# TASK1_1_SCHEM.net
KiCad netlist of a schematic drawn in Altium Designer
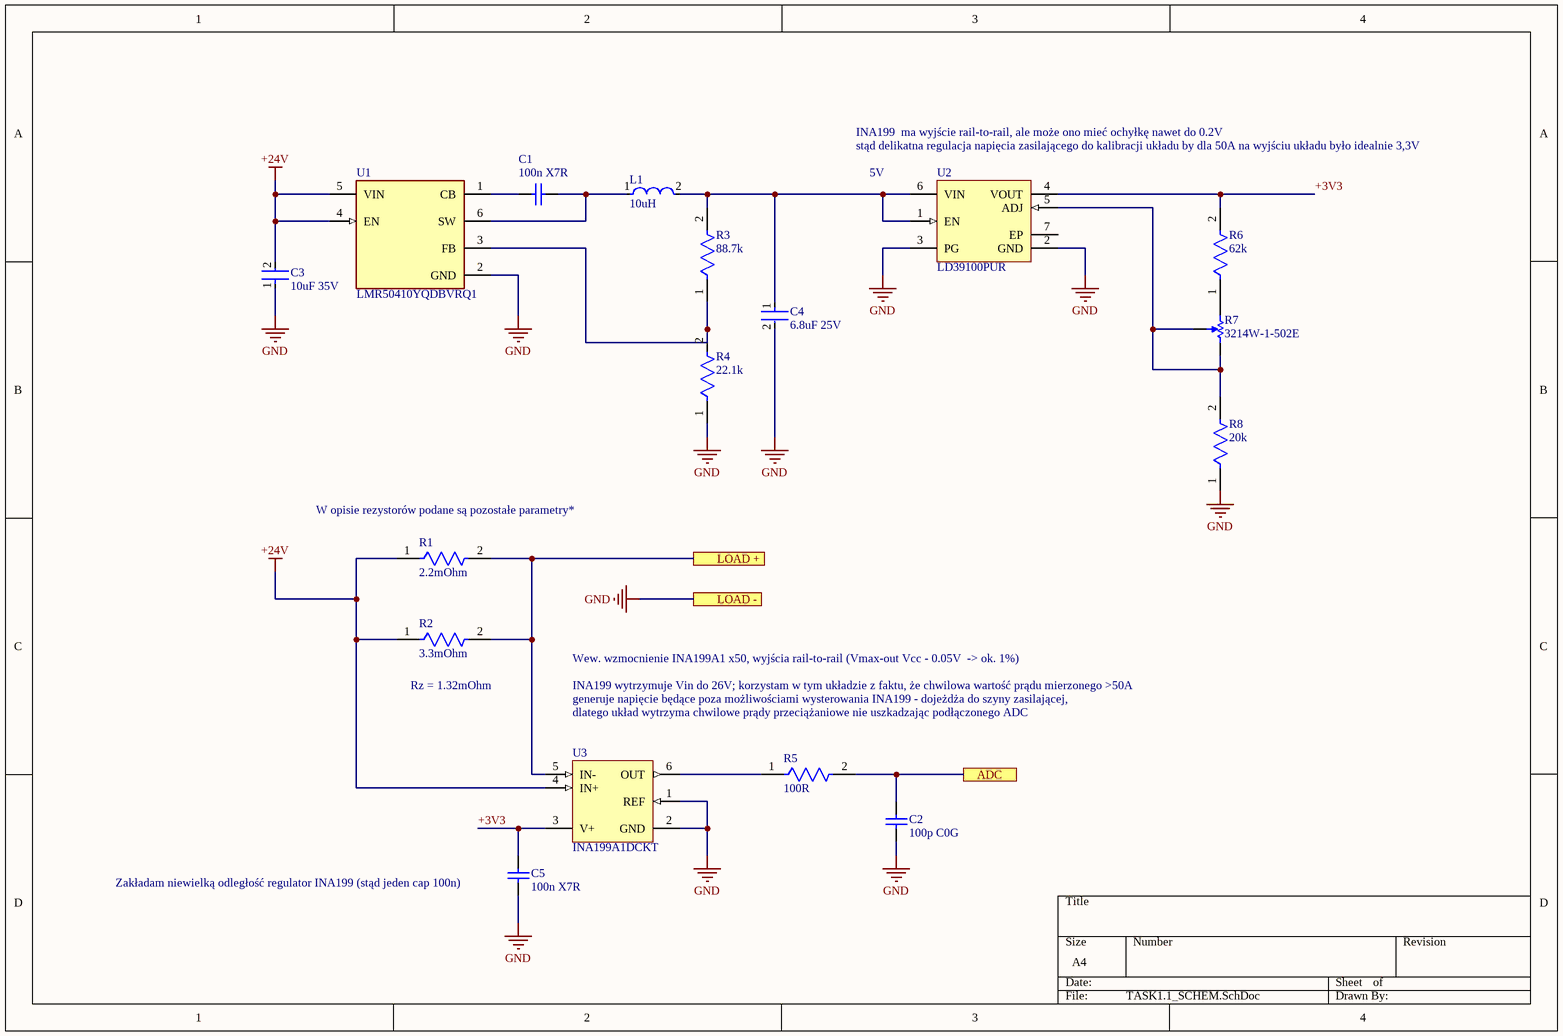
[diagram p0: TASK1.1_SCHEM.SchDoc]

(export (version "E")
  (design (tool "Eeschema 10.0.6"))
  (components
    (comp (ref "C1")
      (value "100n X7R")
      (footprint "CAPC1608X90X35LL15T15")
      (fields
        (field (name "MANUFACTURER") "AVX Interconnect / Elco")
        (field (name "PART NUMBER") "LD035C104KAB2A")
      )
      (libsource (lib "Altium Content Vault") (part "CAP"))
    )
    (comp (ref "C2")
      (value "100p C0G")
      (footprint "CAPC1608X95X40ML15T15")
      (fields (field (name "MANUFACTURER") "Vitramon") (field (name "PART NUMBER") "VJ0603A101JXACW1BC"))
      (libsource (lib "Altium Content Vault") (part "CAP"))
    )
    (comp (ref "C3")
      (value "10uF 35V")
      (footprint "FP-C3216-160-0_2-IPC_C")
      (description "Multilayer Ceramic Capacitors 10uF ±20% 35V X7R SMD 1206")
      (fields (field (name "TOLERANCE") "20%"))
      (libsource (lib "Altium Content Vault") (part "11868f565c42a9108669ba33697ecf6"))
    )
    (comp (ref "C4")
      (value "6.8uF 25V")
      (footprint "FP-C2012-125-0_2-IPC_A")
      (description "Multilayer Ceramic Capacitors 6.8μF ±20% 25V X5R SMD 0805")
      (fields (field (name "TOLERANCE") "20%"))
      (libsource (lib "Altium Content Vault") (part "b4654b650e69147ec39a6b967a45e02"))
    )
    (comp (ref "C5")
      (value "100n X7R")
      (footprint "CAPC1608X90X35LL15T15")
      (fields
        (field (name "MANUFACTURER") "AVX Interconnect / Elco")
        (field (name "PART NUMBER") "LD035C104KAB2A")
      )
      (libsource (lib "Altium Content Vault") (part "CAP"))
    )
    (comp (ref "L1")
      (value "10uH")
      (footprint "FP-NR6045-MFG")
      (description "Shielded Wirewound Inductor 10uH 20% 2.8A 59.8mΩ SMD")
      (fields (field (name "TOLERANCE") "20%"))
      (libsource (lib "Altium Content Vault") (part "725321dda6339637d4d059423bc1c3c"))
    )
    (comp (ref "R1")
      (value "2.2mOhm")
      (footprint "FP-CRCW2512-e3-IPC_C")
      (description "WSL25122L200FEA18\r\nRES 0.0022 OHM 1% 2W 2512")
      (fields (field (name "TOLERANCE") "1%"))
      (libsource (lib "Altium Content Vault") (part "1029c3af85768c4190bb7ad29bc67b5"))
    )
    (comp (ref "R2")
      (value "3.3mOhm")
      (footprint "FP-CRCW2512-e3-IPC_C")
      (description "WSL28163L300FEH\r\nRES 0.0033 OHM 1% 2W 2816")
      (fields (field (name "TOLERANCE") "1%"))
      (libsource (lib "Altium Content Vault") (part "1029c3af85768c4190bb7ad29bc67b5"))
    )
    (comp (ref "R3")
      (value "88.7k")
      (footprint "FP-CRCW0603-e3-MFG")
      (description "RES Thick Film, 88.7kΩ, 1%, 0.1W, 100ppm/°C, 0603")
      (fields (field (name "TOLERANCE") "1%"))
      (libsource (lib "Altium Content Vault") (part "1029c3af85768c4190bb7ad29bc67b5"))
    )
    (comp (ref "R4")
      (value "22.1k")
      (footprint "FP-RP73P-1J-MFG")
      (description "RES SMD 22.1K OHM 0.1% 1/6W 0603")
      (fields (field (name "TOLERANCE") "0.001") (field (name "MANUFACTURER") "TE Connectivity"))
      (libsource (lib "Altium Content Vault") (part "1029c3af85768c4190bb7ad29bc67b5"))
    )
    (comp (ref "R5")
      (value "100R")
      (footprint "FP-ERA3A-IPC_B")
      (description "RES SMD 100 OHM 0.1% 1/10W 0603")
      (fields (field (name "TOLERANCE") "0.1%"))
      (libsource (lib "Altium Content Vault") (part "1029c3af85768c4190bb7ad29bc67b5"))
    )
    (comp (ref "R6")
      (value "62k")
      (footprint "FP-ERJ2RK-MFG")
      (fields (field (name "TOLERANCE") "1%"))
      (libsource (lib "Altium Content Vault") (part "1029c3af85768c4190bb7ad29bc67b5"))
    )
    (comp (ref "R7")
      (value "3214W-1-502E")
      (footprint "BOUR-3214W_V")
      (fields (field (name "MANUFACTURER") "Bourns"))
      (libsource (lib "Altium Content Vault") (part "RES-ADJ-3_A"))
    )
    (comp (ref "R8")
      (value "20k")
      (footprint "FP-RC0402-0_4-MFG")
      (fields (field (name "TOLERANCE") "1%"))
      (libsource (lib "Altium Content Vault") (part "1029c3af85768c4190bb7ad29bc67b5"))
    )
    (comp (ref "U1")
      (value "LMR50410YQDBVRQ1")
      (footprint "FP-DBV0006A-MFG")
      (description "NIXON PLUS-LMR50410YQDBVRQ1")
      (libsource (lib "Altium Content Vault") (part "dd20875c80c3702360114ef84ecc10b"))
    )
    (comp (ref "U2")
      (value "LD39100PUR")
      (footprint "DFN6D_M")
      (libsource (lib "Altium Content Vault") (part "PM-REG-LD39050-SQ7A"))
    )
    (comp (ref "U3")
      (value "INA199A1DCKT")
      (footprint "DCK0006A_N")
      (libsource (lib "Altium Content Vault") (part "TI-INA21X_199A-DCK-6"))
    )
  )
  (nets
    (net (code "1") (name "+24V") (class "Default")
      (node (ref "C3") (pin "2") (pinfunction "2_2") (pintype "passive"))
      (node (ref "R1") (pin "1") (pinfunction "1_1") (pintype "passive"))
      (node (ref "R2") (pin "1") (pinfunction "1_1") (pintype "passive"))
      (node (ref "U1") (pin "4") (pinfunction "EN_4") (pintype "input"))
      (node (ref "U1") (pin "5") (pinfunction "VIN_5") (pintype "power_in"))
      (node (ref "U3") (pin "4") (pinfunction "IN+_4") (pintype "input"))
    )
    (net (code "2") (name "/+3V3") (class "Default")
      (node (ref "C5") (pin "2") (pinfunction "2_2") (pintype "passive"))
      (node (ref "R6") (pin "2") (pinfunction "2_2") (pintype "passive"))
      (node (ref "U2") (pin "4") (pinfunction "VOUT_4") (pintype "power_in"))
      (node (ref "U3") (pin "3") (pinfunction "V+_3") (pintype "power_in"))
    )
    (net (code "3") (name "/ADC") (class "Default")
      (node (ref "C2") (pin "2") (pinfunction "2_2") (pintype "passive"))
      (node (ref "R5") (pin "2") (pinfunction "2_2") (pintype "passive"))
    )
    (net (code "4") (name "/LOAD +") (class "Default")
      (node (ref "R1") (pin "2") (pinfunction "2_2") (pintype "passive"))
      (node (ref "R2") (pin "2") (pinfunction "2_2") (pintype "passive"))
      (node (ref "U3") (pin "5") (pinfunction "IN-_5") (pintype "input"))
    )
    (net (code "5") (name "GND") (class "Default")
      (node (ref "C2") (pin "1") (pinfunction "1_1") (pintype "passive"))
      (node (ref "C3") (pin "1") (pinfunction "1_1") (pintype "passive"))
      (node (ref "C4") (pin "2") (pinfunction "2_2") (pintype "passive"))
      (node (ref "C5") (pin "1") (pinfunction "1_1") (pintype "passive"))
      (node (ref "R4") (pin "1") (pinfunction "1_1") (pintype "passive"))
      (node (ref "R8") (pin "1") (pinfunction "1_1") (pintype "passive"))
      (node (ref "U1") (pin "2") (pinfunction "GND_2") (pintype "power_in"))
      (node (ref "U2") (pin "2") (pinfunction "GND_2") (pintype "power_in"))
      (node (ref "U2") (pin "3") (pinfunction "PG_3") (pintype "open_collector"))
      (node (ref "U3") (pin "1") (pinfunction "REF_1") (pintype "input"))
      (node (ref "U3") (pin "2") (pinfunction "GND_2") (pintype "power_in"))
    )
    (net (code "6") (name "Net-(R6-Pad1)") (class "Default")
      (node (ref "R6") (pin "1") (pinfunction "1_1") (pintype "passive"))
      (node (ref "R7") (pin "1") (pinfunction "1_1") (pintype "passive"))
    )
    (net (code "7") (name "Net-(U1-CB)") (class "Default")
      (node (ref "C1") (pin "1") (pinfunction "1_1") (pintype "passive"))
      (node (ref "U1") (pin "1") (pinfunction "CB_1") (pintype "passive"))
    )
    (net (code "8") (name "Net-(U1-FB)") (class "Default")
      (node (ref "R3") (pin "1") (pinfunction "1_1") (pintype "passive"))
      (node (ref "R4") (pin "2") (pinfunction "2_2") (pintype "passive"))
      (node (ref "U1") (pin "3") (pinfunction "FB_3") (pintype "passive"))
    )
    (net (code "9") (name "Net-(U1-SW)") (class "Default")
      (node (ref "C1") (pin "2") (pinfunction "2_2") (pintype "passive"))
      (node (ref "L1") (pin "1") (pinfunction "1_1") (pintype "passive"))
      (node (ref "U1") (pin "6") (pinfunction "SW_6") (pintype "power_in"))
    )
    (net (code "10") (name "Net-(U2-ADJ)") (class "Default")
      (node (ref "R7") (pin "2") (pinfunction "2_2") (pintype "passive"))
      (node (ref "R7") (pin "3") (pinfunction "3_3") (pintype "passive"))
      (node (ref "R8") (pin "2") (pinfunction "2_2") (pintype "passive"))
      (node (ref "U2") (pin "5") (pinfunction "ADJ_5") (pintype "input"))
    )
    (net (code "11") (name "Net-(U2-EN)") (class "Default")
      (node (ref "C4") (pin "1") (pinfunction "1_1") (pintype "passive"))
      (node (ref "L1") (pin "2") (pinfunction "2_2") (pintype "passive"))
      (node (ref "R3") (pin "2") (pinfunction "2_2") (pintype "passive"))
      (node (ref "U2") (pin "1") (pinfunction "EN_1") (pintype "input"))
      (node (ref "U2") (pin "6") (pinfunction "VIN_6") (pintype "power_in"))
    )
    (net (code "12") (name "Net-(U3-OUT)") (class "Default")
      (node (ref "R5") (pin "1") (pinfunction "1_1") (pintype "passive"))
      (node (ref "U3") (pin "6") (pinfunction "OUT_6") (pintype "output"))
    )
    (net (code "13") (name "unconnected-(U2-EP-Pad7)") (class "Default")
      (node (ref "U2") (pin "7") (pinfunction "EP_7") (pintype "power_in"))
    )
  )
)
